# BadgeLedMatrix.net
KiCad netlist of a schematic drawn in EAGLE
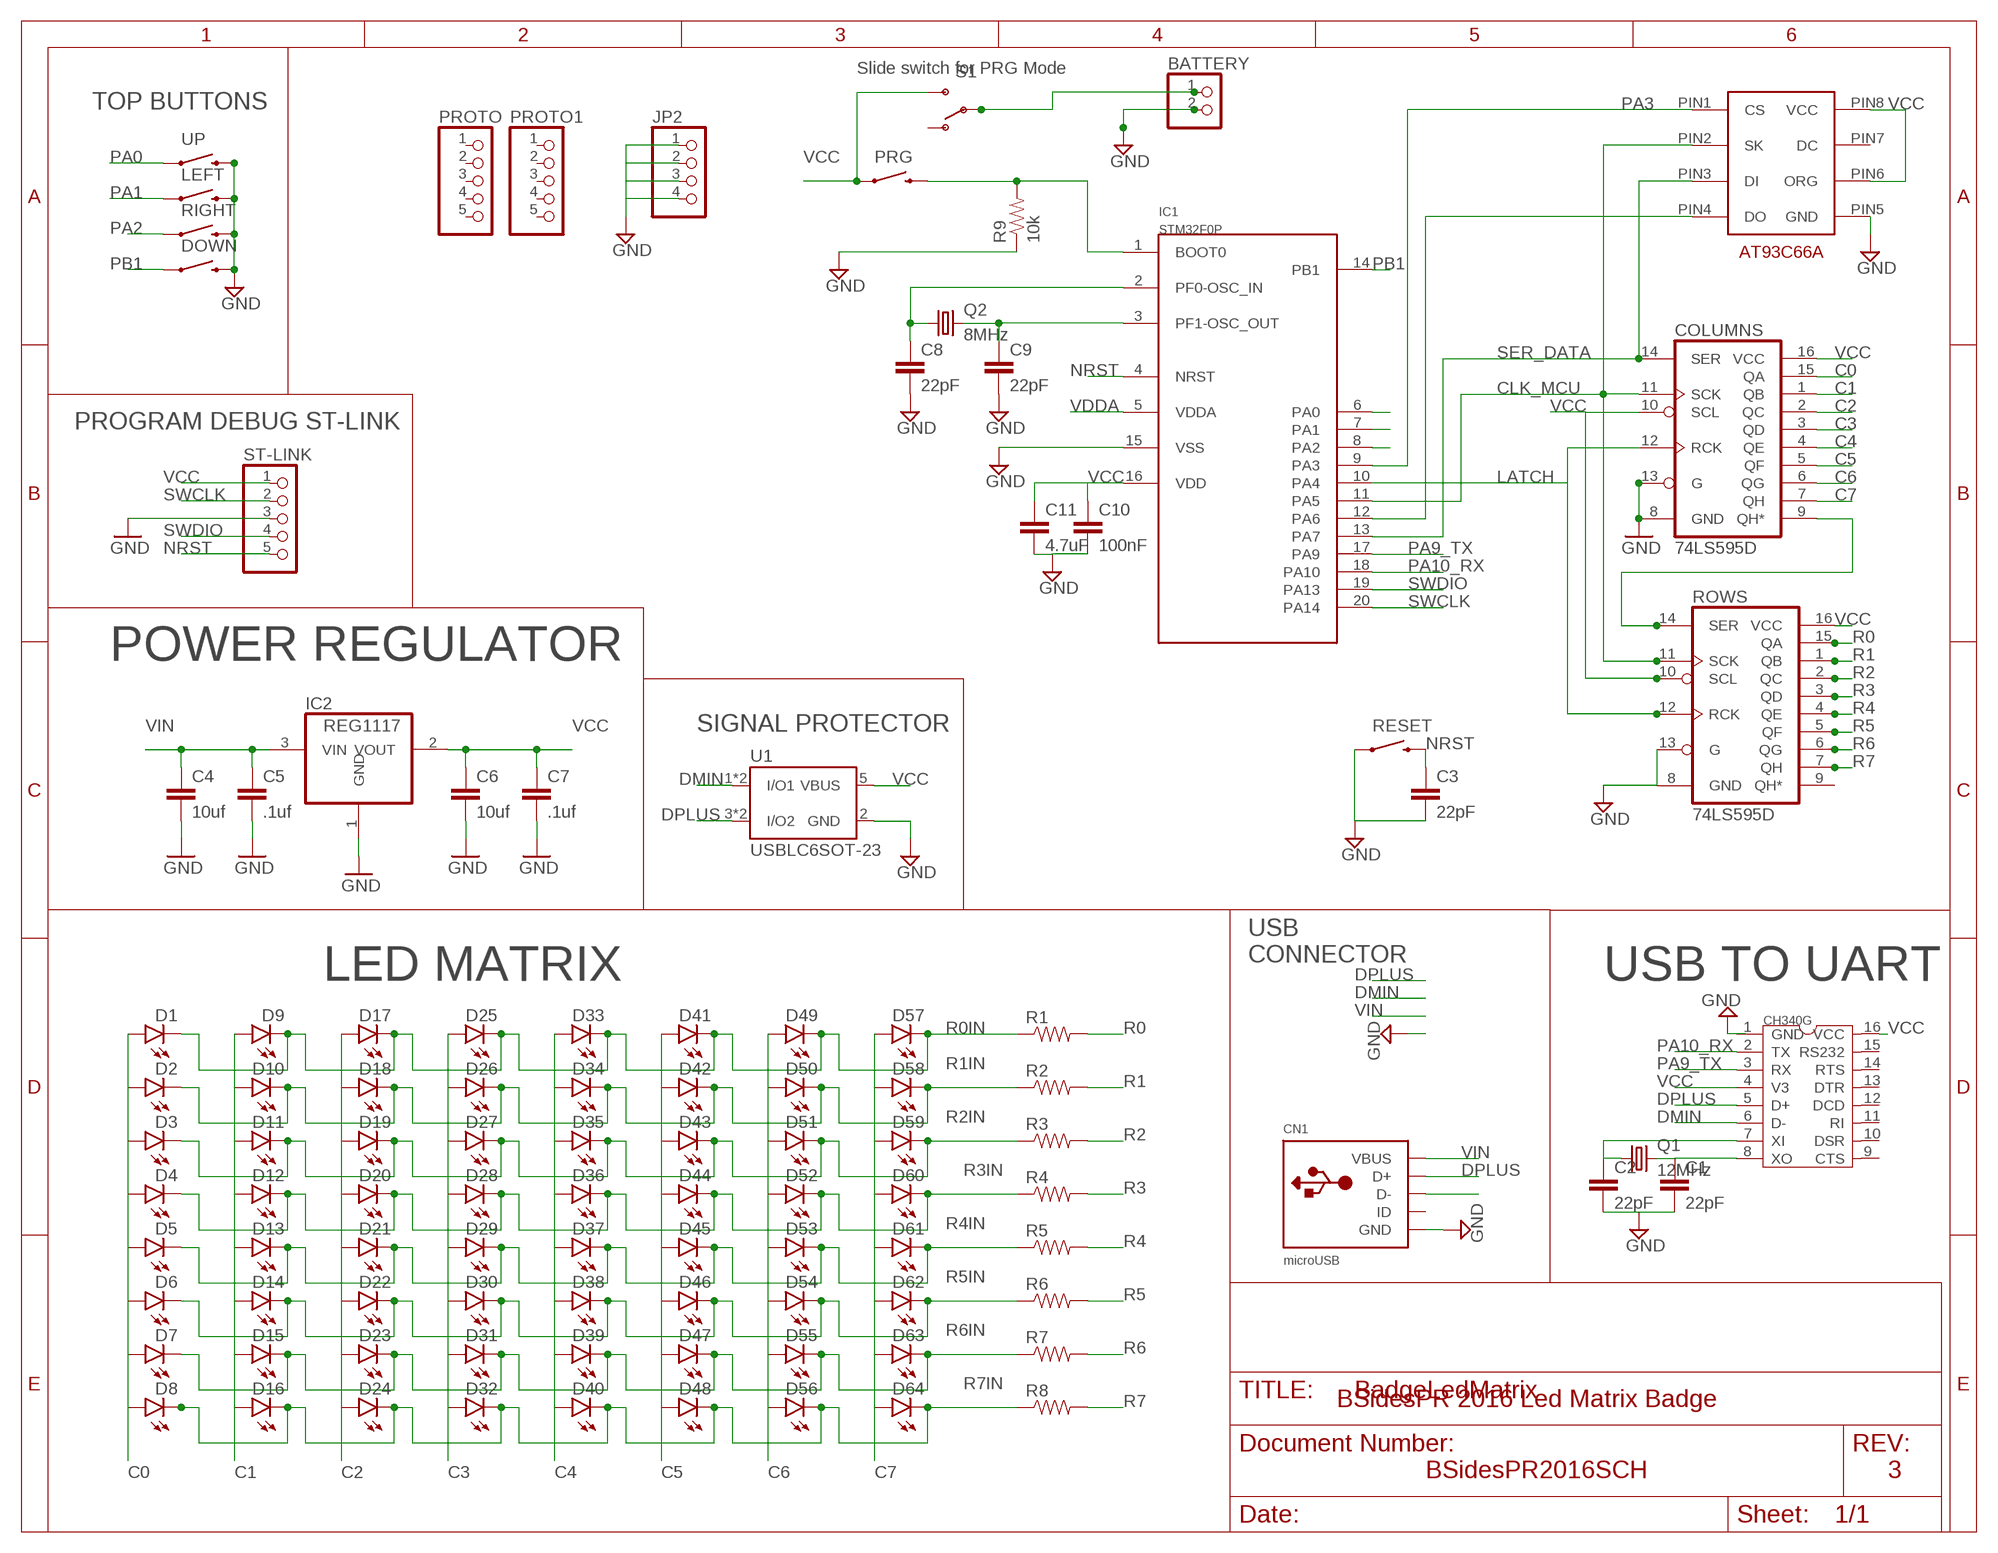
[diagram p0: schematic, sheet 1]

(export (version "E")
  (design (tool "Eeschema 10.0.6"))
  (components
    (comp (ref "BATTERY")
      (value "PINHD-1X2")
      (footprint "eagle-import:1X02")
      (libsource (lib "eagle-import") (part "PINHD-1X2"))
    )
    (comp (ref "C1")
      (value "22pF")
      (footprint "eagle-import:0603-CAP")
      (libsource (lib "eagle-import") (part "CAP0603-CAP"))
    )
    (comp (ref "C2")
      (value "22pF")
      (footprint "eagle-import:0603-CAP")
      (libsource (lib "eagle-import") (part "CAP0603-CAP"))
    )
    (comp (ref "C3")
      (value "22pF")
      (footprint "eagle-import:0603-CAP")
      (libsource (lib "eagle-import") (part "CAP0603-CAP"))
    )
    (comp (ref "C4")
      (value "10uf")
      (footprint "eagle-import:0603-CAP")
      (libsource (lib "eagle-import") (part "SparkFun-Passives_CAP0603-CAP"))
    )
    (comp (ref "C5")
      (value ".1uf")
      (footprint "eagle-import:0603-CAP")
      (libsource (lib "eagle-import") (part "SparkFun-Passives_CAP0603-CAP"))
    )
    (comp (ref "C6")
      (value "10uf")
      (footprint "eagle-import:0603-CAP")
      (libsource (lib "eagle-import") (part "SparkFun-Passives_CAP0603-CAP"))
    )
    (comp (ref "C7")
      (value ".1uf")
      (footprint "eagle-import:0603-CAP")
      (libsource (lib "eagle-import") (part "SparkFun-Passives_CAP0603-CAP"))
    )
    (comp (ref "C8")
      (value "22pF")
      (footprint "eagle-import:0603-CAP")
      (libsource (lib "eagle-import") (part "CAP0603-CAP"))
    )
    (comp (ref "C9")
      (value "22pF")
      (footprint "eagle-import:0603-CAP")
      (libsource (lib "eagle-import") (part "CAP0603-CAP"))
    )
    (comp (ref "C10")
      (value "100nF")
      (footprint "eagle-import:0603-CAP")
      (libsource (lib "eagle-import") (part "CAP0603-CAP"))
    )
    (comp (ref "C11")
      (value "4.7uF")
      (footprint "eagle-import:0603-CAP")
      (libsource (lib "eagle-import") (part "CAP0603-CAP"))
    )
    (comp (ref "CH340G")
      (value "CH340GCH340G")
      (footprint "eagle-import:SOP-16")
      (libsource (lib "eagle-import") (part "CH340GCH340G"))
    )
    (comp (ref "CN1")
      (value "microUSB")
      (footprint "eagle-import:4UCONN_20329")
      (libsource (lib "eagle-import") (part "USBMICRO_20329"))
    )
    (comp (ref "COLUMNS")
      (value "74LS595D")
      (footprint "eagle-import:SO16")
      (libsource (lib "eagle-import") (part "74595DLS"))
    )
    (comp (ref "D1")
      (value "LED0603")
      (footprint "eagle-import:LED-0603")
      (libsource (lib "eagle-import") (part "LED0603"))
    )
    (comp (ref "D2")
      (value "LED0603")
      (footprint "eagle-import:LED-0603")
      (libsource (lib "eagle-import") (part "LED0603"))
    )
    (comp (ref "D3")
      (value "LED0603")
      (footprint "eagle-import:LED-0603")
      (libsource (lib "eagle-import") (part "LED0603"))
    )
    (comp (ref "D4")
      (value "LED0603")
      (footprint "eagle-import:LED-0603")
      (libsource (lib "eagle-import") (part "LED0603"))
    )
    (comp (ref "D5")
      (value "LED0603")
      (footprint "eagle-import:LED-0603")
      (libsource (lib "eagle-import") (part "LED0603"))
    )
    (comp (ref "D6")
      (value "LED0603")
      (footprint "eagle-import:LED-0603")
      (libsource (lib "eagle-import") (part "LED0603"))
    )
    (comp (ref "D7")
      (value "LED0603")
      (footprint "eagle-import:LED-0603")
      (libsource (lib "eagle-import") (part "LED0603"))
    )
    (comp (ref "D8")
      (value "LED0603")
      (footprint "eagle-import:LED-0603")
      (libsource (lib "eagle-import") (part "LED0603"))
    )
    (comp (ref "D9")
      (value "LED0603")
      (footprint "eagle-import:LED-0603")
      (libsource (lib "eagle-import") (part "LED0603"))
    )
    (comp (ref "D10")
      (value "LED0603")
      (footprint "eagle-import:LED-0603")
      (libsource (lib "eagle-import") (part "LED0603"))
    )
    (comp (ref "D11")
      (value "LED0603")
      (footprint "eagle-import:LED-0603")
      (libsource (lib "eagle-import") (part "LED0603"))
    )
    (comp (ref "D12")
      (value "LED0603")
      (footprint "eagle-import:LED-0603")
      (libsource (lib "eagle-import") (part "LED0603"))
    )
    (comp (ref "D13")
      (value "LED0603")
      (footprint "eagle-import:LED-0603")
      (libsource (lib "eagle-import") (part "LED0603"))
    )
    (comp (ref "D14")
      (value "LED0603")
      (footprint "eagle-import:LED-0603")
      (libsource (lib "eagle-import") (part "LED0603"))
    )
    (comp (ref "D15")
      (value "LED0603")
      (footprint "eagle-import:LED-0603")
      (libsource (lib "eagle-import") (part "LED0603"))
    )
    (comp (ref "D16")
      (value "LED0603")
      (footprint "eagle-import:LED-0603")
      (libsource (lib "eagle-import") (part "LED0603"))
    )
    (comp (ref "D17")
      (value "LED0603")
      (footprint "eagle-import:LED-0603")
      (libsource (lib "eagle-import") (part "LED0603"))
    )
    (comp (ref "D18")
      (value "LED0603")
      (footprint "eagle-import:LED-0603")
      (libsource (lib "eagle-import") (part "LED0603"))
    )
    (comp (ref "D19")
      (value "LED0603")
      (footprint "eagle-import:LED-0603")
      (libsource (lib "eagle-import") (part "LED0603"))
    )
    (comp (ref "D20")
      (value "LED0603")
      (footprint "eagle-import:LED-0603")
      (libsource (lib "eagle-import") (part "LED0603"))
    )
    (comp (ref "D21")
      (value "LED0603")
      (footprint "eagle-import:LED-0603")
      (libsource (lib "eagle-import") (part "LED0603"))
    )
    (comp (ref "D22")
      (value "LED0603")
      (footprint "eagle-import:LED-0603")
      (libsource (lib "eagle-import") (part "LED0603"))
    )
    (comp (ref "D23")
      (value "LED0603")
      (footprint "eagle-import:LED-0603")
      (libsource (lib "eagle-import") (part "LED0603"))
    )
    (comp (ref "D24")
      (value "LED0603")
      (footprint "eagle-import:LED-0603")
      (libsource (lib "eagle-import") (part "LED0603"))
    )
    (comp (ref "D25")
      (value "LED0603")
      (footprint "eagle-import:LED-0603")
      (libsource (lib "eagle-import") (part "LED0603"))
    )
    (comp (ref "D26")
      (value "LED0603")
      (footprint "eagle-import:LED-0603")
      (libsource (lib "eagle-import") (part "LED0603"))
    )
    (comp (ref "D27")
      (value "LED0603")
      (footprint "eagle-import:LED-0603")
      (libsource (lib "eagle-import") (part "LED0603"))
    )
    (comp (ref "D28")
      (value "LED0603")
      (footprint "eagle-import:LED-0603")
      (libsource (lib "eagle-import") (part "LED0603"))
    )
    (comp (ref "D29")
      (value "LED0603")
      (footprint "eagle-import:LED-0603")
      (libsource (lib "eagle-import") (part "LED0603"))
    )
    (comp (ref "D30")
      (value "LED0603")
      (footprint "eagle-import:LED-0603")
      (libsource (lib "eagle-import") (part "LED0603"))
    )
    (comp (ref "D31")
      (value "LED0603")
      (footprint "eagle-import:LED-0603")
      (libsource (lib "eagle-import") (part "LED0603"))
    )
    (comp (ref "D32")
      (value "LED0603")
      (footprint "eagle-import:LED-0603")
      (libsource (lib "eagle-import") (part "LED0603"))
    )
    (comp (ref "D33")
      (value "LED0603")
      (footprint "eagle-import:LED-0603")
      (libsource (lib "eagle-import") (part "LED0603"))
    )
    (comp (ref "D34")
      (value "LED0603")
      (footprint "eagle-import:LED-0603")
      (libsource (lib "eagle-import") (part "LED0603"))
    )
    (comp (ref "D35")
      (value "LED0603")
      (footprint "eagle-import:LED-0603")
      (libsource (lib "eagle-import") (part "LED0603"))
    )
    (comp (ref "D36")
      (value "LED0603")
      (footprint "eagle-import:LED-0603")
      (libsource (lib "eagle-import") (part "LED0603"))
    )
    (comp (ref "D37")
      (value "LED0603")
      (footprint "eagle-import:LED-0603")
      (libsource (lib "eagle-import") (part "LED0603"))
    )
    (comp (ref "D38")
      (value "LED0603")
      (footprint "eagle-import:LED-0603")
      (libsource (lib "eagle-import") (part "LED0603"))
    )
    (comp (ref "D39")
      (value "LED0603")
      (footprint "eagle-import:LED-0603")
      (libsource (lib "eagle-import") (part "LED0603"))
    )
    (comp (ref "D40")
      (value "LED0603")
      (footprint "eagle-import:LED-0603")
      (libsource (lib "eagle-import") (part "LED0603"))
    )
    (comp (ref "D41")
      (value "LED0603")
      (footprint "eagle-import:LED-0603")
      (libsource (lib "eagle-import") (part "LED0603"))
    )
    (comp (ref "D42")
      (value "LED0603")
      (footprint "eagle-import:LED-0603")
      (libsource (lib "eagle-import") (part "LED0603"))
    )
    (comp (ref "D43")
      (value "LED0603")
      (footprint "eagle-import:LED-0603")
      (libsource (lib "eagle-import") (part "LED0603"))
    )
    (comp (ref "D44")
      (value "LED0603")
      (footprint "eagle-import:LED-0603")
      (libsource (lib "eagle-import") (part "LED0603"))
    )
    (comp (ref "D45")
      (value "LED0603")
      (footprint "eagle-import:LED-0603")
      (libsource (lib "eagle-import") (part "LED0603"))
    )
    (comp (ref "D46")
      (value "LED0603")
      (footprint "eagle-import:LED-0603")
      (libsource (lib "eagle-import") (part "LED0603"))
    )
    (comp (ref "D47")
      (value "LED0603")
      (footprint "eagle-import:LED-0603")
      (libsource (lib "eagle-import") (part "LED0603"))
    )
    (comp (ref "D48")
      (value "LED0603")
      (footprint "eagle-import:LED-0603")
      (libsource (lib "eagle-import") (part "LED0603"))
    )
    (comp (ref "D49")
      (value "LED0603")
      (footprint "eagle-import:LED-0603")
      (libsource (lib "eagle-import") (part "LED0603"))
    )
    (comp (ref "D50")
      (value "LED0603")
      (footprint "eagle-import:LED-0603")
      (libsource (lib "eagle-import") (part "LED0603"))
    )
    (comp (ref "D51")
      (value "LED0603")
      (footprint "eagle-import:LED-0603")
      (libsource (lib "eagle-import") (part "LED0603"))
    )
    (comp (ref "D52")
      (value "LED0603")
      (footprint "eagle-import:LED-0603")
      (libsource (lib "eagle-import") (part "LED0603"))
    )
    (comp (ref "D53")
      (value "LED0603")
      (footprint "eagle-import:LED-0603")
      (libsource (lib "eagle-import") (part "LED0603"))
    )
    (comp (ref "D54")
      (value "LED0603")
      (footprint "eagle-import:LED-0603")
      (libsource (lib "eagle-import") (part "LED0603"))
    )
    (comp (ref "D55")
      (value "LED0603")
      (footprint "eagle-import:LED-0603")
      (libsource (lib "eagle-import") (part "LED0603"))
    )
    (comp (ref "D56")
      (value "LED0603")
      (footprint "eagle-import:LED-0603")
      (libsource (lib "eagle-import") (part "LED0603"))
    )
    (comp (ref "D57")
      (value "LED0603")
      (footprint "eagle-import:LED-0603")
      (libsource (lib "eagle-import") (part "LED0603"))
    )
    (comp (ref "D58")
      (value "LED0603")
      (footprint "eagle-import:LED-0603")
      (libsource (lib "eagle-import") (part "LED0603"))
    )
    (comp (ref "D59")
      (value "LED0603")
      (footprint "eagle-import:LED-0603")
      (libsource (lib "eagle-import") (part "LED0603"))
    )
    (comp (ref "D60")
      (value "LED0603")
      (footprint "eagle-import:LED-0603")
      (libsource (lib "eagle-import") (part "LED0603"))
    )
    (comp (ref "D61")
      (value "LED0603")
      (footprint "eagle-import:LED-0603")
      (libsource (lib "eagle-import") (part "LED0603"))
    )
    (comp (ref "D62")
      (value "LED0603")
      (footprint "eagle-import:LED-0603")
      (libsource (lib "eagle-import") (part "LED0603"))
    )
    (comp (ref "D63")
      (value "LED0603")
      (footprint "eagle-import:LED-0603")
      (libsource (lib "eagle-import") (part "LED0603"))
    )
    (comp (ref "D64")
      (value "LED0603")
      (footprint "eagle-import:LED-0603")
      (libsource (lib "eagle-import") (part "LED0603"))
    )
    (comp (ref "DOWN")
      (value "SWITCH-MOMENTARY-2SMD-REDUNDANT")
      (footprint "eagle-import:TACTILE-SWITCH-SMD")
      (libsource (lib "eagle-import") (part "SWITCH-MOMENTARY-2SMD-REDUNDANT"))
    )
    (comp (ref "IC1")
      (value "STM32F0P")
      (footprint "eagle-import:TSSOP20")
      (libsource (lib "eagle-import") (part "STM32F0P"))
    )
    (comp (ref "IC2")
      (value "REG1117")
      (footprint "eagle-import:SOT223")
      (libsource (lib "eagle-import") (part "REG1117"))
    )
    (comp (ref "JP2")
      (value "PINHD-1X4")
      (footprint "eagle-import:1X04")
      (libsource (lib "eagle-import") (part "PINHD-1X4"))
    )
    (comp (ref "LEFT")
      (value "SWITCH-MOMENTARY-2SMD-REDUNDANT")
      (footprint "eagle-import:TACTILE-SWITCH-SMD")
      (libsource (lib "eagle-import") (part "SWITCH-MOMENTARY-2SMD-REDUNDANT"))
    )
    (comp (ref "PRG")
      (value "SWITCH-MOMENTARY-2SMD-REDUNDANT")
      (footprint "eagle-import:TACTILE-SWITCH-SMD")
      (libsource (lib "eagle-import") (part "SWITCH-MOMENTARY-2SMD-REDUNDANT"))
    )
    (comp (ref "PROTO")
      (value "PINHD-1X5")
      (footprint "eagle-import:1X05")
      (libsource (lib "eagle-import") (part "PINHD-1X5"))
    )
    (comp (ref "PROTO1")
      (value "PINHD-1X5")
      (footprint "eagle-import:1X05")
      (libsource (lib "eagle-import") (part "PINHD-1X5"))
    )
    (comp (ref "Q1")
      (value "12MHz")
      (footprint "eagle-import:HC49U70")
      (libsource (lib "eagle-import") (part "CRYSTALHC49U70"))
    )
    (comp (ref "Q2")
      (value "8MHz")
      (footprint "eagle-import:HC49U70")
      (libsource (lib "eagle-import") (part "CRYSTALHC49U70"))
    )
    (comp (ref "R1")
      (value "RESISTOR0603-RES")
      (footprint "eagle-import:0603-RES")
      (libsource (lib "eagle-import") (part "RESISTOR0603-RES"))
    )
    (comp (ref "R2")
      (value "RESISTOR0603-RES")
      (footprint "eagle-import:0603-RES")
      (libsource (lib "eagle-import") (part "RESISTOR0603-RES"))
    )
    (comp (ref "R3")
      (value "RESISTOR0603-RES")
      (footprint "eagle-import:0603-RES")
      (libsource (lib "eagle-import") (part "RESISTOR0603-RES"))
    )
    (comp (ref "R4")
      (value "RESISTOR0603-RES")
      (footprint "eagle-import:0603-RES")
      (libsource (lib "eagle-import") (part "RESISTOR0603-RES"))
    )
    (comp (ref "R5")
      (value "RESISTOR0603-RES")
      (footprint "eagle-import:0603-RES")
      (libsource (lib "eagle-import") (part "RESISTOR0603-RES"))
    )
    (comp (ref "R6")
      (value "RESISTOR0603-RES")
      (footprint "eagle-import:0603-RES")
      (libsource (lib "eagle-import") (part "RESISTOR0603-RES"))
    )
    (comp (ref "R7")
      (value "RESISTOR0603-RES")
      (footprint "eagle-import:0603-RES")
      (libsource (lib "eagle-import") (part "RESISTOR0603-RES"))
    )
    (comp (ref "R8")
      (value "RESISTOR0603-RES")
      (footprint "eagle-import:0603-RES")
      (libsource (lib "eagle-import") (part "RESISTOR0603-RES"))
    )
    (comp (ref "R9")
      (value "10k")
      (footprint "eagle-import:0603-RES")
      (libsource (lib "eagle-import") (part "RESISTOR0603-RES"))
    )
    (comp (ref "RESET")
      (value "SWITCH-MOMENTARY-2SMD-REDUNDANT")
      (footprint "eagle-import:TACTILE-SWITCH-SMD")
      (libsource (lib "eagle-import") (part "SWITCH-MOMENTARY-2SMD-REDUNDANT"))
    )
    (comp (ref "RIGHT")
      (value "SWITCH-MOMENTARY-2SMD-REDUNDANT")
      (footprint "eagle-import:TACTILE-SWITCH-SMD")
      (libsource (lib "eagle-import") (part "SWITCH-MOMENTARY-2SMD-REDUNDANT"))
    )
    (comp (ref "ROWS")
      (value "74LS595D")
      (footprint "eagle-import:SO16")
      (libsource (lib "eagle-import") (part "74595DLS"))
    )
    (comp (ref "S1")
      (value "SWITCH-SPDT-SMD-A")
      (footprint "eagle-import:SWITCH-SPST-SMD-A")
      (libsource (lib "eagle-import") (part "SWITCH-SPDT-SMD-A"))
    )
    (comp (ref "ST-LINK")
      (value "PINHD-1X5")
      (footprint "eagle-import:1X05")
      (libsource (lib "eagle-import") (part "PINHD-1X5"))
    )
    (comp (ref "U$6")
      (value "AT93C66A")
      (footprint "eagle-import:SOP-8")
      (libsource (lib "eagle-import") (part "AT93C66A"))
    )
    (comp (ref "U1")
      (value "USBLC6SOT-23")
      (footprint "eagle-import:SOT23-6")
      (libsource (lib "eagle-import") (part "USBLC6SOT-23"))
    )
    (comp (ref "UP")
      (value "SWITCH-MOMENTARY-2SMD-REDUNDANT")
      (footprint "eagle-import:TACTILE-SWITCH-SMD")
      (libsource (lib "eagle-import") (part "SWITCH-MOMENTARY-2SMD-REDUNDANT"))
    )
  )
  (nets
    (net (code "1") (name "/C0") (class "Default")
      (node (ref "COLUMNS") (pin "15") (pinfunction "QA_15") (pintype "tri_state"))
      (node (ref "D1") (pin "A") (pinfunction "A_A") (pintype "passive"))
      (node (ref "D2") (pin "A") (pinfunction "A_A") (pintype "passive"))
      (node (ref "D3") (pin "A") (pinfunction "A_A") (pintype "passive"))
      (node (ref "D4") (pin "A") (pinfunction "A_A") (pintype "passive"))
      (node (ref "D5") (pin "A") (pinfunction "A_A") (pintype "passive"))
      (node (ref "D6") (pin "A") (pinfunction "A_A") (pintype "passive"))
      (node (ref "D7") (pin "A") (pinfunction "A_A") (pintype "passive"))
      (node (ref "D8") (pin "A") (pinfunction "A_A") (pintype "passive"))
    )
    (net (code "2") (name "/C1") (class "Default")
      (node (ref "COLUMNS") (pin "1") (pinfunction "QB_1") (pintype "tri_state"))
      (node (ref "D10") (pin "A") (pinfunction "A_A") (pintype "passive"))
      (node (ref "D11") (pin "A") (pinfunction "A_A") (pintype "passive"))
      (node (ref "D12") (pin "A") (pinfunction "A_A") (pintype "passive"))
      (node (ref "D13") (pin "A") (pinfunction "A_A") (pintype "passive"))
      (node (ref "D14") (pin "A") (pinfunction "A_A") (pintype "passive"))
      (node (ref "D15") (pin "A") (pinfunction "A_A") (pintype "passive"))
      (node (ref "D16") (pin "A") (pinfunction "A_A") (pintype "passive"))
      (node (ref "D9") (pin "A") (pinfunction "A_A") (pintype "passive"))
    )
    (net (code "3") (name "/C2") (class "Default")
      (node (ref "COLUMNS") (pin "2") (pinfunction "QC_2") (pintype "tri_state"))
      (node (ref "D17") (pin "A") (pinfunction "A_A") (pintype "passive"))
      (node (ref "D18") (pin "A") (pinfunction "A_A") (pintype "passive"))
      (node (ref "D19") (pin "A") (pinfunction "A_A") (pintype "passive"))
      (node (ref "D20") (pin "A") (pinfunction "A_A") (pintype "passive"))
      (node (ref "D21") (pin "A") (pinfunction "A_A") (pintype "passive"))
      (node (ref "D22") (pin "A") (pinfunction "A_A") (pintype "passive"))
      (node (ref "D23") (pin "A") (pinfunction "A_A") (pintype "passive"))
      (node (ref "D24") (pin "A") (pinfunction "A_A") (pintype "passive"))
    )
    (net (code "4") (name "/C3") (class "Default")
      (node (ref "COLUMNS") (pin "3") (pinfunction "QD_3") (pintype "tri_state"))
      (node (ref "D25") (pin "A") (pinfunction "A_A") (pintype "passive"))
      (node (ref "D26") (pin "A") (pinfunction "A_A") (pintype "passive"))
      (node (ref "D27") (pin "A") (pinfunction "A_A") (pintype "passive"))
      (node (ref "D28") (pin "A") (pinfunction "A_A") (pintype "passive"))
      (node (ref "D29") (pin "A") (pinfunction "A_A") (pintype "passive"))
      (node (ref "D30") (pin "A") (pinfunction "A_A") (pintype "passive"))
      (node (ref "D31") (pin "A") (pinfunction "A_A") (pintype "passive"))
      (node (ref "D32") (pin "A") (pinfunction "A_A") (pintype "passive"))
    )
    (net (code "5") (name "/C4") (class "Default")
      (node (ref "COLUMNS") (pin "4") (pinfunction "QE_4") (pintype "tri_state"))
      (node (ref "D33") (pin "A") (pinfunction "A_A") (pintype "passive"))
      (node (ref "D34") (pin "A") (pinfunction "A_A") (pintype "passive"))
      (node (ref "D35") (pin "A") (pinfunction "A_A") (pintype "passive"))
      (node (ref "D36") (pin "A") (pinfunction "A_A") (pintype "passive"))
      (node (ref "D37") (pin "A") (pinfunction "A_A") (pintype "passive"))
      (node (ref "D38") (pin "A") (pinfunction "A_A") (pintype "passive"))
      (node (ref "D39") (pin "A") (pinfunction "A_A") (pintype "passive"))
      (node (ref "D40") (pin "A") (pinfunction "A_A") (pintype "passive"))
    )
    (net (code "6") (name "/C5") (class "Default")
      (node (ref "COLUMNS") (pin "5") (pinfunction "QF_5") (pintype "tri_state"))
      (node (ref "D41") (pin "A") (pinfunction "A_A") (pintype "passive"))
      (node (ref "D42") (pin "A") (pinfunction "A_A") (pintype "passive"))
      (node (ref "D43") (pin "A") (pinfunction "A_A") (pintype "passive"))
      (node (ref "D44") (pin "A") (pinfunction "A_A") (pintype "passive"))
      (node (ref "D45") (pin "A") (pinfunction "A_A") (pintype "passive"))
      (node (ref "D46") (pin "A") (pinfunction "A_A") (pintype "passive"))
      (node (ref "D47") (pin "A") (pinfunction "A_A") (pintype "passive"))
      (node (ref "D48") (pin "A") (pinfunction "A_A") (pintype "passive"))
    )
    (net (code "7") (name "/C6") (class "Default")
      (node (ref "COLUMNS") (pin "6") (pinfunction "QG_6") (pintype "tri_state"))
      (node (ref "D49") (pin "A") (pinfunction "A_A") (pintype "passive"))
      (node (ref "D50") (pin "A") (pinfunction "A_A") (pintype "passive"))
      (node (ref "D51") (pin "A") (pinfunction "A_A") (pintype "passive"))
      (node (ref "D52") (pin "A") (pinfunction "A_A") (pintype "passive"))
      (node (ref "D53") (pin "A") (pinfunction "A_A") (pintype "passive"))
      (node (ref "D54") (pin "A") (pinfunction "A_A") (pintype "passive"))
      (node (ref "D55") (pin "A") (pinfunction "A_A") (pintype "passive"))
      (node (ref "D56") (pin "A") (pinfunction "A_A") (pintype "passive"))
    )
    (net (code "8") (name "/C7") (class "Default")
      (node (ref "COLUMNS") (pin "7") (pinfunction "QH_7") (pintype "tri_state"))
      (node (ref "D57") (pin "A") (pinfunction "A_A") (pintype "passive"))
      (node (ref "D58") (pin "A") (pinfunction "A_A") (pintype "passive"))
      (node (ref "D59") (pin "A") (pinfunction "A_A") (pintype "passive"))
      (node (ref "D60") (pin "A") (pinfunction "A_A") (pintype "passive"))
      (node (ref "D61") (pin "A") (pinfunction "A_A") (pintype "passive"))
      (node (ref "D62") (pin "A") (pinfunction "A_A") (pintype "passive"))
      (node (ref "D63") (pin "A") (pinfunction "A_A") (pintype "passive"))
      (node (ref "D64") (pin "A") (pinfunction "A_A") (pintype "passive"))
    )
    (net (code "9") (name "/CLK_MCU") (class "Default")
      (node (ref "COLUMNS") (pin "11") (pinfunction "SCK_11") (pintype "input"))
      (node (ref "IC1") (pin "11") (pinfunction "PA5_11") (pintype "bidirectional"))
      (node (ref "ROWS") (pin "11") (pinfunction "SCK_11") (pintype "input"))
      (node (ref "U$6") (pin "PIN2") (pinfunction "SK_PIN2") (pintype "bidirectional"))
    )
    (net (code "10") (name "/DMIN") (class "Default")
      (node (ref "CH340G") (pin "6") (pinfunction "D-_6") (pintype "bidirectional"))
      (node (ref "CN1") (pin "D-") (pinfunction "D-_D-") (pintype "bidirectional"))
      (node (ref "U1") (pin "1") (pinfunction "I/O1_1") (pintype "bidirectional"))
      (node (ref "U1") (pin "4") (pinfunction "I/O1_4") (pintype "bidirectional"))
    )
    (net (code "11") (name "/DPLUS") (class "Default")
      (node (ref "CH340G") (pin "5") (pinfunction "D+_5") (pintype "bidirectional"))
      (node (ref "CN1") (pin "D+") (pinfunction "D+_D+") (pintype "bidirectional"))
      (node (ref "U1") (pin "3") (pinfunction "I/O2_3") (pintype "bidirectional"))
      (node (ref "U1") (pin "6") (pinfunction "I/O2_6") (pintype "bidirectional"))
    )
    (net (code "12") (name "/LATCH") (class "Default")
      (node (ref "COLUMNS") (pin "12") (pinfunction "RCK_12") (pintype "input"))
      (node (ref "IC1") (pin "10") (pinfunction "PA4_10") (pintype "bidirectional"))
      (node (ref "ROWS") (pin "12") (pinfunction "RCK_12") (pintype "input"))
    )
    (net (code "13") (name "/NRST") (class "Default")
      (node (ref "C3") (pin "1") (pinfunction "1_1") (pintype "passive"))
      (node (ref "IC1") (pin "4") (pinfunction "NRST_4") (pintype "bidirectional"))
      (node (ref "RESET") (pin "3") (pinfunction "2_3") (pintype "passive"))
      (node (ref "RESET") (pin "4") (pinfunction "2_4") (pintype "passive"))
      (node (ref "ST-LINK") (pin "5") (pinfunction "5_5") (pintype "passive"))
    )
    (net (code "14") (name "/PA0") (class "Default")
      (node (ref "IC1") (pin "6") (pinfunction "PA0_6") (pintype "bidirectional"))
      (node (ref "UP") (pin "1") (pinfunction "1_1") (pintype "passive"))
      (node (ref "UP") (pin "2") (pinfunction "1_2") (pintype "passive"))
    )
    (net (code "15") (name "/PA1") (class "Default")
      (node (ref "IC1") (pin "7") (pinfunction "PA1_7") (pintype "bidirectional"))
      (node (ref "LEFT") (pin "1") (pinfunction "1_1") (pintype "passive"))
      (node (ref "LEFT") (pin "2") (pinfunction "1_2") (pintype "passive"))
    )
    (net (code "16") (name "/PA2") (class "Default")
      (node (ref "IC1") (pin "8") (pinfunction "PA2_8") (pintype "bidirectional"))
      (node (ref "RIGHT") (pin "1") (pinfunction "1_1") (pintype "passive"))
      (node (ref "RIGHT") (pin "2") (pinfunction "1_2") (pintype "passive"))
    )
    (net (code "17") (name "/PA3") (class "Default")
      (node (ref "IC1") (pin "9") (pinfunction "PA3_9") (pintype "bidirectional"))
      (node (ref "U$6") (pin "PIN1") (pinfunction "CS_PIN1") (pintype "bidirectional"))
    )
    (net (code "18") (name "/PA9_TX") (class "Default")
      (node (ref "CH340G") (pin "3") (pinfunction "RX_3") (pintype "bidirectional"))
      (node (ref "IC1") (pin "17") (pinfunction "PA9_17") (pintype "bidirectional"))
    )
    (net (code "19") (name "/PA10_RX") (class "Default")
      (node (ref "CH340G") (pin "2") (pinfunction "TX_2") (pintype "bidirectional"))
      (node (ref "IC1") (pin "18") (pinfunction "PA10_18") (pintype "bidirectional"))
    )
    (net (code "20") (name "/PB1") (class "Default")
      (node (ref "DOWN") (pin "1") (pinfunction "1_1") (pintype "passive"))
      (node (ref "DOWN") (pin "2") (pinfunction "1_2") (pintype "passive"))
      (node (ref "IC1") (pin "14") (pinfunction "PB1_14") (pintype "bidirectional"))
    )
    (net (code "21") (name "/R0") (class "Default")
      (node (ref "R1") (pin "2") (pinfunction "2_2") (pintype "passive"))
      (node (ref "ROWS") (pin "15") (pinfunction "QA_15") (pintype "tri_state"))
    )
    (net (code "22") (name "/R0IN") (class "Default")
      (node (ref "D1") (pin "C") (pinfunction "C_C") (pintype "passive"))
      (node (ref "D17") (pin "C") (pinfunction "C_C") (pintype "passive"))
      (node (ref "D25") (pin "C") (pinfunction "C_C") (pintype "passive"))
      (node (ref "D33") (pin "C") (pinfunction "C_C") (pintype "passive"))
      (node (ref "D41") (pin "C") (pinfunction "C_C") (pintype "passive"))
      (node (ref "D49") (pin "C") (pinfunction "C_C") (pintype "passive"))
      (node (ref "D57") (pin "C") (pinfunction "C_C") (pintype "passive"))
      (node (ref "D9") (pin "C") (pinfunction "C_C") (pintype "passive"))
      (node (ref "R1") (pin "1") (pinfunction "1_1") (pintype "passive"))
    )
    (net (code "23") (name "/R1") (class "Default")
      (node (ref "R2") (pin "2") (pinfunction "2_2") (pintype "passive"))
      (node (ref "ROWS") (pin "1") (pinfunction "QB_1") (pintype "tri_state"))
    )
    (net (code "24") (name "/R1IN") (class "Default")
      (node (ref "D10") (pin "C") (pinfunction "C_C") (pintype "passive"))
      (node (ref "D18") (pin "C") (pinfunction "C_C") (pintype "passive"))
      (node (ref "D2") (pin "C") (pinfunction "C_C") (pintype "passive"))
      (node (ref "D26") (pin "C") (pinfunction "C_C") (pintype "passive"))
      (node (ref "D34") (pin "C") (pinfunction "C_C") (pintype "passive"))
      (node (ref "D42") (pin "C") (pinfunction "C_C") (pintype "passive"))
      (node (ref "D50") (pin "C") (pinfunction "C_C") (pintype "passive"))
      (node (ref "D58") (pin "C") (pinfunction "C_C") (pintype "passive"))
      (node (ref "R2") (pin "1") (pinfunction "1_1") (pintype "passive"))
    )
    (net (code "25") (name "/R2") (class "Default")
      (node (ref "R3") (pin "2") (pinfunction "2_2") (pintype "passive"))
      (node (ref "ROWS") (pin "2") (pinfunction "QC_2") (pintype "tri_state"))
    )
    (net (code "26") (name "/R2IN") (class "Default")
      (node (ref "D11") (pin "C") (pinfunction "C_C") (pintype "passive"))
      (node (ref "D19") (pin "C") (pinfunction "C_C") (pintype "passive"))
      (node (ref "D27") (pin "C") (pinfunction "C_C") (pintype "passive"))
      (node (ref "D3") (pin "C") (pinfunction "C_C") (pintype "passive"))
      (node (ref "D35") (pin "C") (pinfunction "C_C") (pintype "passive"))
      (node (ref "D43") (pin "C") (pinfunction "C_C") (pintype "passive"))
      (node (ref "D51") (pin "C") (pinfunction "C_C") (pintype "passive"))
      (node (ref "D59") (pin "C") (pinfunction "C_C") (pintype "passive"))
      (node (ref "R3") (pin "1") (pinfunction "1_1") (pintype "passive"))
    )
    (net (code "27") (name "/R3") (class "Default")
      (node (ref "R4") (pin "2") (pinfunction "2_2") (pintype "passive"))
      (node (ref "ROWS") (pin "3") (pinfunction "QD_3") (pintype "tri_state"))
    )
    (net (code "28") (name "/R3IN") (class "Default")
      (node (ref "D12") (pin "C") (pinfunction "C_C") (pintype "passive"))
      (node (ref "D20") (pin "C") (pinfunction "C_C") (pintype "passive"))
      (node (ref "D28") (pin "C") (pinfunction "C_C") (pintype "passive"))
      (node (ref "D36") (pin "C") (pinfunction "C_C") (pintype "passive"))
      (node (ref "D4") (pin "C") (pinfunction "C_C") (pintype "passive"))
      (node (ref "D44") (pin "C") (pinfunction "C_C") (pintype "passive"))
      (node (ref "D52") (pin "C") (pinfunction "C_C") (pintype "passive"))
      (node (ref "D60") (pin "C") (pinfunction "C_C") (pintype "passive"))
      (node (ref "R4") (pin "1") (pinfunction "1_1") (pintype "passive"))
    )
    (net (code "29") (name "/R4") (class "Default")
      (node (ref "R5") (pin "2") (pinfunction "2_2") (pintype "passive"))
      (node (ref "ROWS") (pin "4") (pinfunction "QE_4") (pintype "tri_state"))
    )
    (net (code "30") (name "/R4IN") (class "Default")
      (node (ref "D13") (pin "C") (pinfunction "C_C") (pintype "passive"))
      (node (ref "D21") (pin "C") (pinfunction "C_C") (pintype "passive"))
      (node (ref "D29") (pin "C") (pinfunction "C_C") (pintype "passive"))
      (node (ref "D37") (pin "C") (pinfunction "C_C") (pintype "passive"))
      (node (ref "D45") (pin "C") (pinfunction "C_C") (pintype "passive"))
      (node (ref "D5") (pin "C") (pinfunction "C_C") (pintype "passive"))
      (node (ref "D53") (pin "C") (pinfunction "C_C") (pintype "passive"))
      (node (ref "D61") (pin "C") (pinfunction "C_C") (pintype "passive"))
      (node (ref "R5") (pin "1") (pinfunction "1_1") (pintype "passive"))
    )
    (net (code "31") (name "/R5") (class "Default")
      (node (ref "R6") (pin "2") (pinfunction "2_2") (pintype "passive"))
      (node (ref "ROWS") (pin "5") (pinfunction "QF_5") (pintype "tri_state"))
    )
    (net (code "32") (name "/R5IN") (class "Default")
      (node (ref "D14") (pin "C") (pinfunction "C_C") (pintype "passive"))
      (node (ref "D22") (pin "C") (pinfunction "C_C") (pintype "passive"))
      (node (ref "D30") (pin "C") (pinfunction "C_C") (pintype "passive"))
      (node (ref "D38") (pin "C") (pinfunction "C_C") (pintype "passive"))
      (node (ref "D46") (pin "C") (pinfunction "C_C") (pintype "passive"))
      (node (ref "D54") (pin "C") (pinfunction "C_C") (pintype "passive"))
      (node (ref "D6") (pin "C") (pinfunction "C_C") (pintype "passive"))
      (node (ref "D62") (pin "C") (pinfunction "C_C") (pintype "passive"))
      (node (ref "R6") (pin "1") (pinfunction "1_1") (pintype "passive"))
    )
    (net (code "33") (name "/R6") (class "Default")
      (node (ref "R7") (pin "2") (pinfunction "2_2") (pintype "passive"))
      (node (ref "ROWS") (pin "6") (pinfunction "QG_6") (pintype "tri_state"))
    )
    (net (code "34") (name "/R6IN") (class "Default")
      (node (ref "D15") (pin "C") (pinfunction "C_C") (pintype "passive"))
      (node (ref "D23") (pin "C") (pinfunction "C_C") (pintype "passive"))
      (node (ref "D31") (pin "C") (pinfunction "C_C") (pintype "passive"))
      (node (ref "D39") (pin "C") (pinfunction "C_C") (pintype "passive"))
      (node (ref "D47") (pin "C") (pinfunction "C_C") (pintype "passive"))
      (node (ref "D55") (pin "C") (pinfunction "C_C") (pintype "passive"))
      (node (ref "D63") (pin "C") (pinfunction "C_C") (pintype "passive"))
      (node (ref "D7") (pin "C") (pinfunction "C_C") (pintype "passive"))
      (node (ref "R7") (pin "1") (pinfunction "1_1") (pintype "passive"))
    )
    (net (code "35") (name "/R7") (class "Default")
      (node (ref "R8") (pin "2") (pinfunction "2_2") (pintype "passive"))
      (node (ref "ROWS") (pin "7") (pinfunction "QH_7") (pintype "tri_state"))
    )
    (net (code "36") (name "/R7IN") (class "Default")
      (node (ref "D16") (pin "C") (pinfunction "C_C") (pintype "passive"))
      (node (ref "D24") (pin "C") (pinfunction "C_C") (pintype "passive"))
      (node (ref "D32") (pin "C") (pinfunction "C_C") (pintype "passive"))
      (node (ref "D40") (pin "C") (pinfunction "C_C") (pintype "passive"))
      (node (ref "D48") (pin "C") (pinfunction "C_C") (pintype "passive"))
      (node (ref "D56") (pin "C") (pinfunction "C_C") (pintype "passive"))
      (node (ref "D64") (pin "C") (pinfunction "C_C") (pintype "passive"))
      (node (ref "D8") (pin "C") (pinfunction "C_C") (pintype "passive"))
      (node (ref "R8") (pin "1") (pinfunction "1_1") (pintype "passive"))
    )
    (net (code "37") (name "/RI") (class "Default")
      (node (ref "CH340G") (pin "11") (pinfunction "RI_11") (pintype "power_in"))
    )
    (net (code "38") (name "/SER_DATA") (class "Default")
      (node (ref "COLUMNS") (pin "14") (pinfunction "SER_14") (pintype "input"))
      (node (ref "IC1") (pin "13") (pinfunction "PA7_13") (pintype "bidirectional"))
      (node (ref "U$6") (pin "PIN3") (pinfunction "DI_PIN3") (pintype "bidirectional"))
    )
    (net (code "39") (name "/SWCLK") (class "Default")
      (node (ref "IC1") (pin "20") (pinfunction "PA14_20") (pintype "bidirectional"))
      (node (ref "ST-LINK") (pin "2") (pinfunction "2_2") (pintype "passive"))
    )
    (net (code "40") (name "/SWDIO") (class "Default")
      (node (ref "IC1") (pin "19") (pinfunction "PA13_19") (pintype "bidirectional"))
      (node (ref "ST-LINK") (pin "4") (pinfunction "4_4") (pintype "passive"))
    )
    (net (code "41") (name "/VCC") (class "Default")
      (node (ref "C10") (pin "1") (pinfunction "1_1") (pintype "passive"))
      (node (ref "C11") (pin "1") (pinfunction "1_1") (pintype "passive"))
      (node (ref "C6") (pin "1") (pinfunction "1_1") (pintype "passive"))
      (node (ref "C7") (pin "1") (pinfunction "1_1") (pintype "passive"))
      (node (ref "CH340G") (pin "16") (pinfunction "VCC_16") (pintype "output"))
      (node (ref "CH340G") (pin "4") (pinfunction "V3_4") (pintype "bidirectional"))
      (node (ref "COLUMNS") (pin "10") (pinfunction "SCL_10") (pintype "input"))
      (node (ref "COLUMNS") (pin "16") (pinfunction "VCC_16") (pintype "power_in"))
      (node (ref "IC1") (pin "16") (pinfunction "VDD_16") (pintype "bidirectional"))
      (node (ref "IC2") (pin "2") (pinfunction "VOUT_2") (pintype "output"))
      (node (ref "PRG") (pin "1") (pinfunction "1_1") (pintype "passive"))
      (node (ref "PRG") (pin "2") (pinfunction "1_2") (pintype "passive"))
      (node (ref "ROWS") (pin "10") (pinfunction "SCL_10") (pintype "input"))
      (node (ref "ROWS") (pin "16") (pinfunction "VCC_16") (pintype "power_in"))
      (node (ref "S1") (pin "3") (pinfunction "S_3") (pintype "passive"))
      (node (ref "ST-LINK") (pin "1") (pinfunction "1_1") (pintype "passive"))
      (node (ref "U$6") (pin "PIN6") (pinfunction "ORG_PIN6") (pintype "bidirectional"))
      (node (ref "U$6") (pin "PIN8") (pinfunction "VCC_PIN8") (pintype "bidirectional"))
      (node (ref "U1") (pin "5") (pinfunction "VBUS_5") (pintype "bidirectional"))
    )
    (net (code "42") (name "/VDDA") (class "Default")
      (node (ref "IC1") (pin "5") (pinfunction "VDDA_5") (pintype "bidirectional"))
    )
    (net (code "43") (name "/VIN") (class "Default")
      (node (ref "C4") (pin "1") (pinfunction "1_1") (pintype "passive"))
      (node (ref "C5") (pin "1") (pinfunction "1_1") (pintype "passive"))
      (node (ref "CN1") (pin "VBUS") (pinfunction "VBUS_VBUS") (pintype "power_in"))
      (node (ref "IC2") (pin "3") (pinfunction "VIN_3") (pintype "input"))
    )
    (net (code "44") (name "GND") (class "Default")
      (node (ref "BATTERY") (pin "2") (pinfunction "2_2") (pintype "passive"))
      (node (ref "C1") (pin "2") (pinfunction "2_2") (pintype "passive"))
      (node (ref "C10") (pin "2") (pinfunction "2_2") (pintype "passive"))
      (node (ref "C11") (pin "2") (pinfunction "2_2") (pintype "passive"))
      (node (ref "C2") (pin "2") (pinfunction "2_2") (pintype "passive"))
      (node (ref "C3") (pin "2") (pinfunction "2_2") (pintype "passive"))
      (node (ref "C4") (pin "2") (pinfunction "2_2") (pintype "passive"))
      (node (ref "C5") (pin "2") (pinfunction "2_2") (pintype "passive"))
      (node (ref "C6") (pin "2") (pinfunction "2_2") (pintype "passive"))
      (node (ref "C7") (pin "2") (pinfunction "2_2") (pintype "passive"))
      (node (ref "C8") (pin "2") (pinfunction "2_2") (pintype "passive"))
      (node (ref "C9") (pin "2") (pinfunction "2_2") (pintype "passive"))
      (node (ref "CH340G") (pin "1") (pinfunction "GND_1") (pintype "bidirectional"))
      (node (ref "CN1") (pin "BASE@1") (pinfunction "GND_BASE@1") (pintype "power_in"))
      (node (ref "CN1") (pin "BASE@2") (pinfunction "GND_BASE@2") (pintype "power_in"))
      (node (ref "CN1") (pin "GND") (pinfunction "GND_GND") (pintype "power_in"))
      (node (ref "CN1") (pin "SPRT@1") (pinfunction "GND_SPRT@1") (pintype "power_in"))
      (node (ref "CN1") (pin "SPRT@2") (pinfunction "GND_SPRT@2") (pintype "power_in"))
      (node (ref "CN1") (pin "SPRT@3") (pinfunction "GND_SPRT@3") (pintype "power_in"))
      (node (ref "CN1") (pin "SPRT@4") (pinfunction "GND_SPRT@4") (pintype "power_in"))
      (node (ref "COLUMNS") (pin "13") (pinfunction "G_13") (pintype "input"))
      (node (ref "COLUMNS") (pin "8") (pinfunction "GND_8") (pintype "power_in"))
      (node (ref "DOWN") (pin "3") (pinfunction "2_3") (pintype "passive"))
      (node (ref "DOWN") (pin "4") (pinfunction "2_4") (pintype "passive"))
      (node (ref "IC1") (pin "15") (pinfunction "VSS_15") (pintype "bidirectional"))
      (node (ref "IC2") (pin "1") (pinfunction "GND_1") (pintype "power_in"))
      (node (ref "JP2") (pin "1") (pinfunction "1_1") (pintype "passive"))
      (node (ref "JP2") (pin "2") (pinfunction "2_2") (pintype "passive"))
      (node (ref "JP2") (pin "3") (pinfunction "3_3") (pintype "passive"))
      (node (ref "JP2") (pin "4") (pinfunction "4_4") (pintype "passive"))
      (node (ref "LEFT") (pin "3") (pinfunction "2_3") (pintype "passive"))
      (node (ref "LEFT") (pin "4") (pinfunction "2_4") (pintype "passive"))
      (node (ref "R9") (pin "1") (pinfunction "1_1") (pintype "passive"))
      (node (ref "RESET") (pin "1") (pinfunction "1_1") (pintype "passive"))
      (node (ref "RESET") (pin "2") (pinfunction "1_2") (pintype "passive"))
      (node (ref "RIGHT") (pin "3") (pinfunction "2_3") (pintype "passive"))
      (node (ref "RIGHT") (pin "4") (pinfunction "2_4") (pintype "passive"))
      (node (ref "ROWS") (pin "13") (pinfunction "G_13") (pintype "input"))
      (node (ref "ROWS") (pin "8") (pinfunction "GND_8") (pintype "power_in"))
      (node (ref "ST-LINK") (pin "3") (pinfunction "3_3") (pintype "passive"))
      (node (ref "U$6") (pin "PIN5") (pinfunction "GND_PIN5") (pintype "bidirectional"))
      (node (ref "U1") (pin "2") (pinfunction "GND_2") (pintype "bidirectional"))
      (node (ref "UP") (pin "3") (pinfunction "2_3") (pintype "passive"))
      (node (ref "UP") (pin "4") (pinfunction "2_4") (pintype "passive"))
    )
    (net (code "45") (name "Net-(CH340G-XI)") (class "Default")
      (node (ref "C2") (pin "1") (pinfunction "1_1") (pintype "passive"))
      (node (ref "CH340G") (pin "7") (pinfunction "XI_7") (pintype "power_in"))
      (node (ref "Q1") (pin "1") (pinfunction "1_1") (pintype "passive"))
    )
    (net (code "46") (name "Net-(CH340G-XO)") (class "Default")
      (node (ref "C1") (pin "1") (pinfunction "1_1") (pintype "passive"))
      (node (ref "CH340G") (pin "8") (pinfunction "XO_8") (pintype "input"))
      (node (ref "Q1") (pin "2") (pinfunction "2_2") (pintype "passive"))
    )
    (net (code "47") (name "Net-(COLUMNS-QH*)") (class "Default")
      (node (ref "COLUMNS") (pin "9") (pinfunction "QH*_9") (pintype "tri_state"))
      (node (ref "ROWS") (pin "14") (pinfunction "SER_14") (pintype "input"))
    )
    (net (code "48") (name "Net-(IC1-BOOT0)") (class "Default")
      (node (ref "IC1") (pin "1") (pinfunction "BOOT0_1") (pintype "bidirectional"))
      (node (ref "PRG") (pin "3") (pinfunction "2_3") (pintype "passive"))
      (node (ref "PRG") (pin "4") (pinfunction "2_4") (pintype "passive"))
      (node (ref "R9") (pin "2") (pinfunction "2_2") (pintype "passive"))
    )
    (net (code "49") (name "Net-(IC1-PA6)") (class "Default")
      (node (ref "IC1") (pin "12") (pinfunction "PA6_12") (pintype "bidirectional"))
      (node (ref "U$6") (pin "PIN4") (pinfunction "DO_PIN4") (pintype "bidirectional"))
    )
    (net (code "50") (name "Net-(IC1-PF0-OSC_IN)") (class "Default")
      (node (ref "C8") (pin "1") (pinfunction "1_1") (pintype "passive"))
      (node (ref "IC1") (pin "2") (pinfunction "PF0-OSC_IN_2") (pintype "bidirectional"))
      (node (ref "Q2") (pin "1") (pinfunction "1_1") (pintype "passive"))
    )
    (net (code "51") (name "Net-(IC1-PF1-OSC_OUT)") (class "Default")
      (node (ref "C9") (pin "1") (pinfunction "1_1") (pintype "passive"))
      (node (ref "IC1") (pin "3") (pinfunction "PF1-OSC_OUT_3") (pintype "bidirectional"))
      (node (ref "Q2") (pin "2") (pinfunction "2_2") (pintype "passive"))
    )
    (net (code "52") (name "Net-(S1-P)") (class "Default")
      (node (ref "BATTERY") (pin "1") (pinfunction "1_1") (pintype "passive"))
      (node (ref "S1") (pin "2") (pinfunction "P_2") (pintype "passive"))
    )
    (net (code "53") (name "unconnected-(CH340G-CTS-Pad9)") (class "Default")
      (node (ref "CH340G") (pin "9") (pinfunction "CTS_9") (pintype "bidirectional"))
    )
    (net (code "54") (name "unconnected-(CH340G-DCD-Pad12)") (class "Default")
      (node (ref "CH340G") (pin "12") (pinfunction "DCD_12") (pintype "output"))
    )
    (net (code "55") (name "unconnected-(CH340G-DSR-Pad10)") (class "Default")
      (node (ref "CH340G") (pin "10") (pinfunction "DSR_10") (pintype "bidirectional"))
    )
    (net (code "56") (name "unconnected-(CH340G-DTR-Pad13)") (class "Default")
      (node (ref "CH340G") (pin "13") (pinfunction "DTR_13") (pintype "input"))
    )
    (net (code "57") (name "unconnected-(CH340G-RS232-Pad15)") (class "Default")
      (node (ref "CH340G") (pin "15") (pinfunction "RS232_15") (pintype "input"))
    )
    (net (code "58") (name "unconnected-(CH340G-RTS-Pad14)") (class "Default")
      (node (ref "CH340G") (pin "14") (pinfunction "RTS_14") (pintype "input"))
    )
    (net (code "59") (name "unconnected-(CN1-PadID)") (class "Default")
      (node (ref "CN1") (pin "ID") (pinfunction "ID_ID") (pintype "bidirectional"))
    )
    (net (code "60") (name "unconnected-(PROTO-Pad1)") (class "Default")
      (node (ref "PROTO") (pin "1") (pinfunction "1_1") (pintype "passive"))
    )
    (net (code "61") (name "unconnected-(PROTO-Pad2)") (class "Default")
      (node (ref "PROTO") (pin "2") (pinfunction "2_2") (pintype "passive"))
    )
    (net (code "62") (name "unconnected-(PROTO-Pad3)") (class "Default")
      (node (ref "PROTO") (pin "3") (pinfunction "3_3") (pintype "passive"))
    )
    (net (code "63") (name "unconnected-(PROTO-Pad4)") (class "Default")
      (node (ref "PROTO") (pin "4") (pinfunction "4_4") (pintype "passive"))
    )
    (net (code "64") (name "unconnected-(PROTO-Pad5)") (class "Default")
      (node (ref "PROTO") (pin "5") (pinfunction "5_5") (pintype "passive"))
    )
    (net (code "65") (name "unconnected-(PROTO1-Pad1)") (class "Default")
      (node (ref "PROTO1") (pin "1") (pinfunction "1_1") (pintype "passive"))
    )
    (net (code "66") (name "unconnected-(PROTO1-Pad2)") (class "Default")
      (node (ref "PROTO1") (pin "2") (pinfunction "2_2") (pintype "passive"))
    )
    (net (code "67") (name "unconnected-(PROTO1-Pad3)") (class "Default")
      (node (ref "PROTO1") (pin "3") (pinfunction "3_3") (pintype "passive"))
    )
    (net (code "68") (name "unconnected-(PROTO1-Pad4)") (class "Default")
      (node (ref "PROTO1") (pin "4") (pinfunction "4_4") (pintype "passive"))
    )
    (net (code "69") (name "unconnected-(PROTO1-Pad5)") (class "Default")
      (node (ref "PROTO1") (pin "5") (pinfunction "5_5") (pintype "passive"))
    )
    (net (code "70") (name "unconnected-(ROWS-QH*-Pad9)") (class "Default")
      (node (ref "ROWS") (pin "9") (pinfunction "QH*_9") (pintype "tri_state"))
    )
    (net (code "71") (name "unconnected-(S1-O-Pad1)") (class "Default")
      (node (ref "S1") (pin "1") (pinfunction "O_1") (pintype "passive"))
    )
    (net (code "72") (name "unconnected-(U$6-DC-PadPIN7)") (class "Default")
      (node (ref "U$6") (pin "PIN7") (pinfunction "DC_PIN7") (pintype "bidirectional"))
    )
  )
)
